# atmegademo.net
KiCad netlist of a schematic drawn in EAGLE
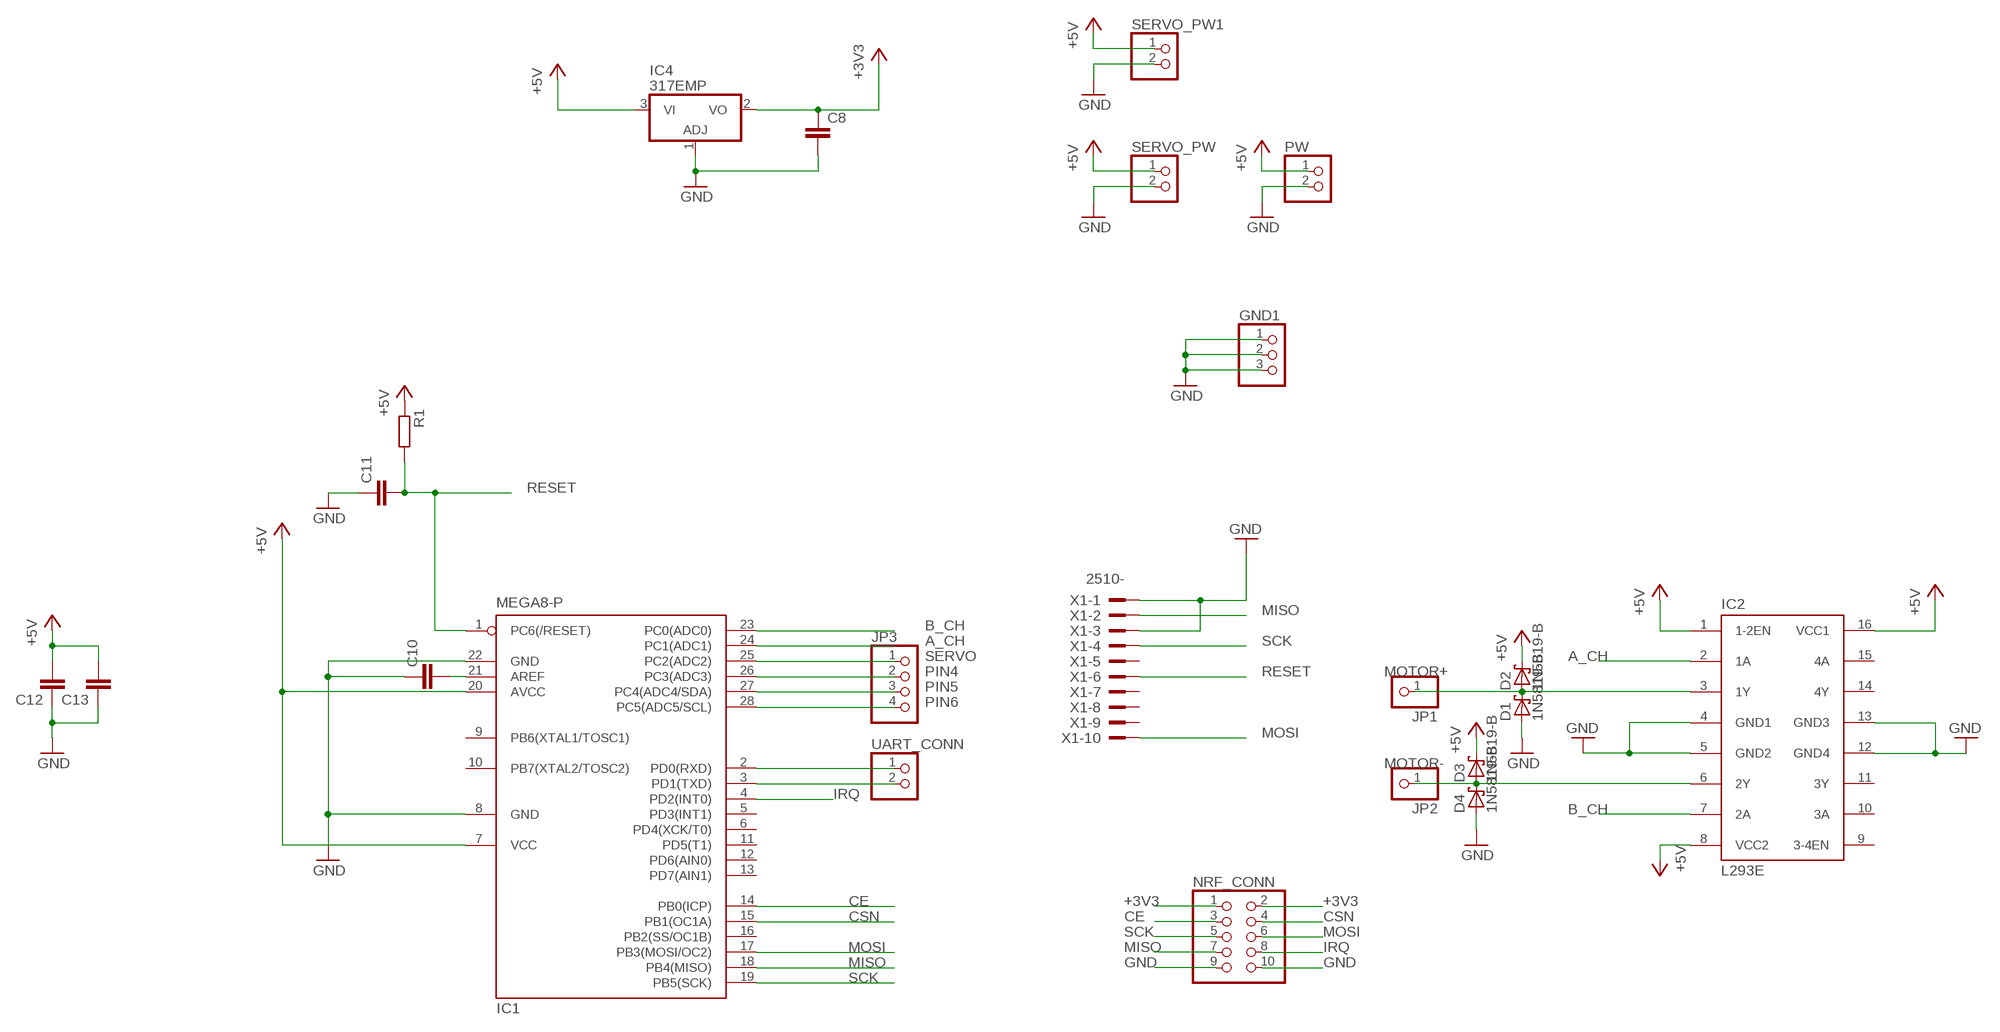
[diagram p0: schematic, sheet 1]

(export (version "E")
  (design (tool "Eeschema 10.0.6"))
  (components
    (comp (ref "C8")
      (value "C-EUC0805K")
      (footprint "eagle-import:C0805K")
      (libsource (lib "eagle-import") (part "C-EUC0805K"))
    )
    (comp (ref "C10")
      (value "C-EUC0805K")
      (footprint "eagle-import:C0805K")
      (libsource (lib "eagle-import") (part "C-EUC0805K"))
    )
    (comp (ref "C11")
      (value "C-EUC0805K")
      (footprint "eagle-import:C0805K")
      (libsource (lib "eagle-import") (part "C-EUC0805K"))
    )
    (comp (ref "C12")
      (value "C-EUC0805K")
      (footprint "eagle-import:C0805K")
      (libsource (lib "eagle-import") (part "C-EUC0805K"))
    )
    (comp (ref "C13")
      (value "C-EUC0805K")
      (footprint "eagle-import:C0805K")
      (libsource (lib "eagle-import") (part "C-EUC0805K"))
    )
    (comp (ref "D1")
      (value "1N5819-B")
      (footprint "eagle-import:DO41-7.6")
      (libsource (lib "eagle-import") (part "1N5819-B"))
    )
    (comp (ref "D2")
      (value "1N5819-B")
      (footprint "eagle-import:DO41-7.6")
      (libsource (lib "eagle-import") (part "1N5819-B"))
    )
    (comp (ref "D3")
      (value "1N5819-B")
      (footprint "eagle-import:DO41-7.6")
      (libsource (lib "eagle-import") (part "1N5819-B"))
    )
    (comp (ref "D4")
      (value "1N5819-B")
      (footprint "eagle-import:DO41-7.6")
      (libsource (lib "eagle-import") (part "1N5819-B"))
    )
    (comp (ref "GND1")
      (value "PINHD-1X3")
      (footprint "eagle-import:1X03")
      (libsource (lib "eagle-import") (part "PINHD-1X3"))
    )
    (comp (ref "IC1")
      (value "MEGA8-P")
      (footprint "eagle-import:DIL28-3")
      (libsource (lib "eagle-import") (part "MEGA8-P"))
    )
    (comp (ref "IC2")
      (value "L293E")
      (footprint "eagle-import:DIL16")
      (fields (field (name "MF") "Arrow Electronics"))
      (libsource (lib "eagle-import") (part "L293E"))
    )
    (comp (ref "IC4")
      (value "317EMP")
      (footprint "eagle-import:SOT223")
      (libsource (lib "eagle-import") (part "317EMP"))
    )
    (comp (ref "JP1")
      (value "PINHD-1X1")
      (footprint "eagle-import:1X01")
      (libsource (lib "eagle-import") (part "PINHD-1X1"))
    )
    (comp (ref "JP2")
      (value "PINHD-1X1")
      (footprint "eagle-import:1X01")
      (libsource (lib "eagle-import") (part "PINHD-1X1"))
    )
    (comp (ref "JP3")
      (value "PINHD-1X4")
      (footprint "eagle-import:1X04")
      (libsource (lib "eagle-import") (part "PINHD-1X4"))
    )
    (comp (ref "NRF_CONN")
      (value "PINHD-2X5")
      (footprint "eagle-import:2X05")
      (libsource (lib "eagle-import") (part "PINHD-2X5"))
    )
    (comp (ref "PW")
      (value "PINHD-1X2")
      (footprint "eagle-import:1X02")
      (libsource (lib "eagle-import") (part "PINHD-1X2"))
    )
    (comp (ref "R1")
      (value "R-EU_0207/10")
      (footprint "eagle-import:0207_10")
      (libsource (lib "eagle-import") (part "R-EU_0207/10"))
    )
    (comp (ref "SERVO_PW")
      (value "PINHD-1X2")
      (footprint "eagle-import:1X02")
      (libsource (lib "eagle-import") (part "PINHD-1X2"))
    )
    (comp (ref "SERVO_PW1")
      (value "PINHD-1X2")
      (footprint "eagle-import:1X02")
      (libsource (lib "eagle-import") (part "PINHD-1X2"))
    )
    (comp (ref "UART_CONN")
      (value "PINHD-1X2")
      (footprint "eagle-import:1X02")
      (libsource (lib "eagle-import") (part "PINHD-1X2"))
    )
    (comp (ref "X1")
      (value "2510-")
      (footprint "eagle-import:PAK100_2500-10")
      (fields (field (name "MF") "3M") (field (name "MPN") "2510-6002UB"))
      (libsource (lib "eagle-import") (part "2510-"))
    )
  )
  (nets
    (net (code "1") (name "+3V3") (class "Default")
      (node (ref "C8") (pin "1") (pinfunction "1_1") (pintype "passive"))
      (node (ref "IC4") (pin "2") (pinfunction "VO_2") (pintype "passive"))
      (node (ref "NRF_CONN") (pin "1") (pinfunction "1_1") (pintype "passive"))
      (node (ref "NRF_CONN") (pin "2") (pinfunction "2_2") (pintype "passive"))
    )
    (net (code "2") (name "+5V") (class "Default")
      (node (ref "C12") (pin "2") (pinfunction "2_2") (pintype "passive"))
      (node (ref "C13") (pin "2") (pinfunction "2_2") (pintype "passive"))
      (node (ref "D2") (pin "C") (pinfunction "C_C") (pintype "passive"))
      (node (ref "D3") (pin "C") (pinfunction "C_C") (pintype "passive"))
      (node (ref "IC1") (pin "20") (pinfunction "AVCC_20") (pintype "power_in"))
      (node (ref "IC1") (pin "7") (pinfunction "VCC_7") (pintype "power_in"))
      (node (ref "IC2") (pin "1") (pinfunction "1-2EN_1") (pintype "input"))
      (node (ref "IC2") (pin "16") (pinfunction "VCC1_16") (pintype "power_in"))
      (node (ref "IC2") (pin "8") (pinfunction "VCC2_8") (pintype "power_in"))
      (node (ref "IC4") (pin "3") (pinfunction "VI_3") (pintype "input"))
      (node (ref "PW") (pin "1") (pinfunction "1_1") (pintype "passive"))
      (node (ref "R1") (pin "1") (pinfunction "1_1") (pintype "passive"))
      (node (ref "SERVO_PW") (pin "1") (pinfunction "1_1") (pintype "passive"))
      (node (ref "SERVO_PW1") (pin "1") (pinfunction "1_1") (pintype "passive"))
    )
    (net (code "3") (name "/A_CH") (class "Default")
      (node (ref "IC1") (pin "24") (pinfunction "PC1(ADC1)_24") (pintype "bidirectional"))
      (node (ref "IC2") (pin "2") (pinfunction "1A_2") (pintype "input"))
    )
    (net (code "4") (name "/B_CH") (class "Default")
      (node (ref "IC1") (pin "23") (pinfunction "PC0(ADC0)_23") (pintype "bidirectional"))
      (node (ref "IC2") (pin "7") (pinfunction "2A_7") (pintype "input"))
    )
    (net (code "5") (name "/CE") (class "Default")
      (node (ref "IC1") (pin "14") (pinfunction "PB0(ICP)_14") (pintype "bidirectional"))
      (node (ref "NRF_CONN") (pin "3") (pinfunction "3_3") (pintype "passive"))
    )
    (net (code "6") (name "/CSN") (class "Default")
      (node (ref "IC1") (pin "15") (pinfunction "PB1(OC1A)_15") (pintype "bidirectional"))
      (node (ref "NRF_CONN") (pin "4") (pinfunction "4_4") (pintype "passive"))
    )
    (net (code "7") (name "/IRQ") (class "Default")
      (node (ref "IC1") (pin "4") (pinfunction "PD2(INT0)_4") (pintype "bidirectional"))
      (node (ref "NRF_CONN") (pin "8") (pinfunction "8_8") (pintype "passive"))
    )
    (net (code "8") (name "/MISO") (class "Default")
      (node (ref "IC1") (pin "18") (pinfunction "PB4(MISO)_18") (pintype "bidirectional"))
      (node (ref "NRF_CONN") (pin "7") (pinfunction "7_7") (pintype "passive"))
      (node (ref "X1") (pin "2") (pinfunction "KL_2") (pintype "passive"))
    )
    (net (code "9") (name "/MOSI") (class "Default")
      (node (ref "IC1") (pin "17") (pinfunction "PB3(MOSI/OC2)_17") (pintype "bidirectional"))
      (node (ref "NRF_CONN") (pin "6") (pinfunction "6_6") (pintype "passive"))
      (node (ref "X1") (pin "10") (pinfunction "KL_10") (pintype "passive"))
    )
    (net (code "10") (name "/MOTOR+") (class "Default")
      (node (ref "D1") (pin "C") (pinfunction "C_C") (pintype "passive"))
      (node (ref "D2") (pin "A") (pinfunction "A_A") (pintype "passive"))
      (node (ref "IC2") (pin "3") (pinfunction "1Y_3") (pintype "output"))
      (node (ref "JP1") (pin "1") (pinfunction "1_1") (pintype "passive"))
    )
    (net (code "11") (name "/MOTOR-") (class "Default")
      (node (ref "D3") (pin "A") (pinfunction "A_A") (pintype "passive"))
      (node (ref "D4") (pin "C") (pinfunction "C_C") (pintype "passive"))
      (node (ref "IC2") (pin "6") (pinfunction "2Y_6") (pintype "output"))
      (node (ref "JP2") (pin "1") (pinfunction "1_1") (pintype "passive"))
    )
    (net (code "12") (name "/PIN4") (class "Default")
      (node (ref "IC1") (pin "26") (pinfunction "PC3(ADC3)_26") (pintype "bidirectional"))
      (node (ref "JP3") (pin "2") (pinfunction "2_2") (pintype "passive"))
    )
    (net (code "13") (name "/PIN5") (class "Default")
      (node (ref "IC1") (pin "27") (pinfunction "PC4(ADC4/SDA)_27") (pintype "bidirectional"))
      (node (ref "JP3") (pin "3") (pinfunction "3_3") (pintype "passive"))
    )
    (net (code "14") (name "/PIN6") (class "Default")
      (node (ref "IC1") (pin "28") (pinfunction "PC5(ADC5/SCL)_28") (pintype "bidirectional"))
      (node (ref "JP3") (pin "4") (pinfunction "4_4") (pintype "passive"))
    )
    (net (code "15") (name "/RESET") (class "Default")
      (node (ref "C11") (pin "2") (pinfunction "2_2") (pintype "passive"))
      (node (ref "IC1") (pin "1") (pinfunction "PC6(/RESET)_1") (pintype "bidirectional"))
      (node (ref "R1") (pin "2") (pinfunction "2_2") (pintype "passive"))
      (node (ref "X1") (pin "6") (pinfunction "KL_6") (pintype "passive"))
    )
    (net (code "16") (name "/SCK") (class "Default")
      (node (ref "IC1") (pin "19") (pinfunction "PB5(SCK)_19") (pintype "bidirectional"))
      (node (ref "NRF_CONN") (pin "5") (pinfunction "5_5") (pintype "passive"))
      (node (ref "X1") (pin "4") (pinfunction "KL_4") (pintype "passive"))
    )
    (net (code "17") (name "/SERVO") (class "Default")
      (node (ref "IC1") (pin "25") (pinfunction "PC2(ADC2)_25") (pintype "bidirectional"))
      (node (ref "JP3") (pin "1") (pinfunction "1_1") (pintype "passive"))
    )
    (net (code "18") (name "GND") (class "Default")
      (node (ref "C10") (pin "1") (pinfunction "1_1") (pintype "passive"))
      (node (ref "C11") (pin "1") (pinfunction "1_1") (pintype "passive"))
      (node (ref "C12") (pin "1") (pinfunction "1_1") (pintype "passive"))
      (node (ref "C13") (pin "1") (pinfunction "1_1") (pintype "passive"))
      (node (ref "C8") (pin "2") (pinfunction "2_2") (pintype "passive"))
      (node (ref "D1") (pin "A") (pinfunction "A_A") (pintype "passive"))
      (node (ref "D4") (pin "A") (pinfunction "A_A") (pintype "passive"))
      (node (ref "GND1") (pin "1") (pinfunction "1_1") (pintype "passive"))
      (node (ref "GND1") (pin "2") (pinfunction "2_2") (pintype "passive"))
      (node (ref "GND1") (pin "3") (pinfunction "3_3") (pintype "passive"))
      (node (ref "IC1") (pin "22") (pinfunction "GND_22") (pintype "power_in"))
      (node (ref "IC1") (pin "8") (pinfunction "GND_8") (pintype "power_in"))
      (node (ref "IC2") (pin "12") (pinfunction "GND4_12") (pintype "power_in"))
      (node (ref "IC2") (pin "13") (pinfunction "GND3_13") (pintype "power_in"))
      (node (ref "IC2") (pin "4") (pinfunction "GND1_4") (pintype "power_in"))
      (node (ref "IC2") (pin "5") (pinfunction "GND2_5") (pintype "power_in"))
      (node (ref "IC4") (pin "1") (pinfunction "ADJ_1") (pintype "input"))
      (node (ref "NRF_CONN") (pin "10") (pinfunction "10_10") (pintype "passive"))
      (node (ref "NRF_CONN") (pin "9") (pinfunction "9_9") (pintype "passive"))
      (node (ref "PW") (pin "2") (pinfunction "2_2") (pintype "passive"))
      (node (ref "SERVO_PW") (pin "2") (pinfunction "2_2") (pintype "passive"))
      (node (ref "SERVO_PW1") (pin "2") (pinfunction "2_2") (pintype "passive"))
      (node (ref "X1") (pin "1") (pinfunction "KL_1") (pintype "passive"))
      (node (ref "X1") (pin "3") (pinfunction "KL_3") (pintype "passive"))
    )
    (net (code "19") (name "Net-(IC1-AREF)") (class "Default")
      (node (ref "C10") (pin "2") (pinfunction "2_2") (pintype "passive"))
      (node (ref "IC1") (pin "21") (pinfunction "AREF_21") (pintype "passive"))
    )
    (net (code "20") (name "Net-(IC1-PD0(RXD))") (class "Default")
      (node (ref "IC1") (pin "2") (pinfunction "PD0(RXD)_2") (pintype "bidirectional"))
      (node (ref "UART_CONN") (pin "1") (pinfunction "1_1") (pintype "passive"))
    )
    (net (code "21") (name "Net-(IC1-PD1(TXD))") (class "Default")
      (node (ref "IC1") (pin "3") (pinfunction "PD1(TXD)_3") (pintype "bidirectional"))
      (node (ref "UART_CONN") (pin "2") (pinfunction "2_2") (pintype "passive"))
    )
    (net (code "22") (name "unconnected-(IC1-PB2(SS{slash}OC1B)-Pad16)") (class "Default")
      (node (ref "IC1") (pin "16") (pinfunction "PB2(SS/OC1B)_16") (pintype "bidirectional"))
    )
    (net (code "23") (name "unconnected-(IC1-PB6(XTAL1{slash}TOSC1)-Pad9)") (class "Default")
      (node (ref "IC1") (pin "9") (pinfunction "PB6(XTAL1/TOSC1)_9") (pintype "bidirectional"))
    )
    (net (code "24") (name "unconnected-(IC1-PB7(XTAL2{slash}TOSC2)-Pad10)") (class "Default")
      (node (ref "IC1") (pin "10") (pinfunction "PB7(XTAL2/TOSC2)_10") (pintype "bidirectional"))
    )
    (net (code "25") (name "unconnected-(IC1-PD3(INT1)-Pad5)") (class "Default")
      (node (ref "IC1") (pin "5") (pinfunction "PD3(INT1)_5") (pintype "bidirectional"))
    )
    (net (code "26") (name "unconnected-(IC1-PD4(XCK{slash}T0)-Pad6)") (class "Default")
      (node (ref "IC1") (pin "6") (pinfunction "PD4(XCK/T0)_6") (pintype "bidirectional"))
    )
    (net (code "27") (name "unconnected-(IC1-PD5(T1)-Pad11)") (class "Default")
      (node (ref "IC1") (pin "11") (pinfunction "PD5(T1)_11") (pintype "bidirectional"))
    )
    (net (code "28") (name "unconnected-(IC1-PD6(AIN0)-Pad12)") (class "Default")
      (node (ref "IC1") (pin "12") (pinfunction "PD6(AIN0)_12") (pintype "bidirectional"))
    )
    (net (code "29") (name "unconnected-(IC1-PD7(AIN1)-Pad13)") (class "Default")
      (node (ref "IC1") (pin "13") (pinfunction "PD7(AIN1)_13") (pintype "bidirectional"))
    )
    (net (code "30") (name "unconnected-(IC2-3-4EN-Pad9)") (class "Default")
      (node (ref "IC2") (pin "9") (pinfunction "3-4EN_9") (pintype "input"))
    )
    (net (code "31") (name "unconnected-(IC2-3A-Pad10)") (class "Default")
      (node (ref "IC2") (pin "10") (pinfunction "3A_10") (pintype "input"))
    )
    (net (code "32") (name "unconnected-(IC2-3Y-Pad11)") (class "Default")
      (node (ref "IC2") (pin "11") (pinfunction "3Y_11") (pintype "output"))
    )
    (net (code "33") (name "unconnected-(IC2-4A-Pad15)") (class "Default")
      (node (ref "IC2") (pin "15") (pinfunction "4A_15") (pintype "input"))
    )
    (net (code "34") (name "unconnected-(IC2-4Y-Pad14)") (class "Default")
      (node (ref "IC2") (pin "14") (pinfunction "4Y_14") (pintype "output"))
    )
    (net (code "35") (name "unconnected-(X1F-KL-Pad5)") (class "Default")
      (node (ref "X1") (pin "5") (pinfunction "KL_5") (pintype "passive"))
    )
    (net (code "36") (name "unconnected-(X1H-KL-Pad7)") (class "Default")
      (node (ref "X1") (pin "7") (pinfunction "KL_7") (pintype "passive"))
    )
    (net (code "37") (name "unconnected-(X1I-KL-Pad8)") (class "Default")
      (node (ref "X1") (pin "8") (pinfunction "KL_8") (pintype "passive"))
    )
    (net (code "38") (name "unconnected-(X1J-KL-Pad9)") (class "Default")
      (node (ref "X1") (pin "9") (pinfunction "KL_9") (pintype "passive"))
    )
  )
)
